# test_strip_v0_1_r1_1.net
KiCad netlist of a schematic drawn in EAGLE
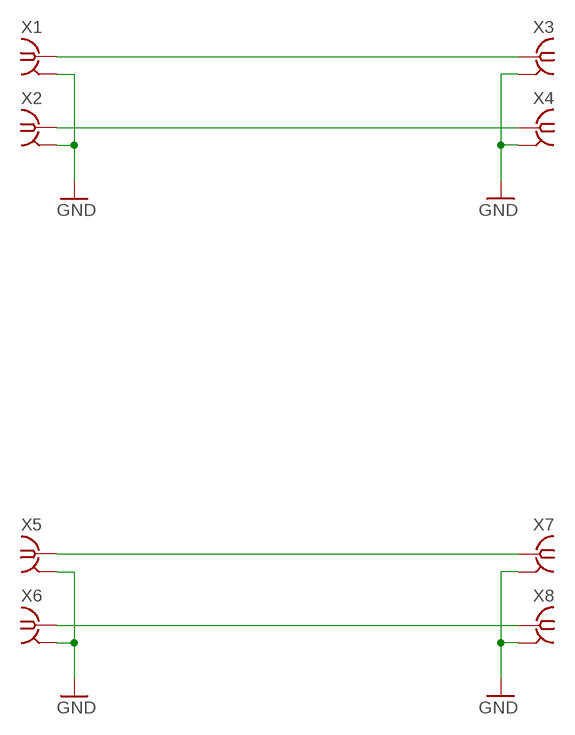
[diagram p0: schematic, sheet 1]

(export (version "E")
  (design (tool "Eeschema 10.0.6"))
  (components
    (comp (ref "X1")
      (value "BU-SMA-E-ND")
      (footprint "eagle-import:SMA-EDGE_ND")
      (libsource (lib "eagle-import") (part "BU-SMA-E-ND"))
    )
    (comp (ref "X2")
      (value "BU-SMA-E-ND")
      (footprint "eagle-import:SMA-EDGE_ND")
      (libsource (lib "eagle-import") (part "BU-SMA-E-ND"))
    )
    (comp (ref "X3")
      (value "BU-SMA-E-ND")
      (footprint "eagle-import:SMA-EDGE_ND")
      (libsource (lib "eagle-import") (part "BU-SMA-E-ND"))
    )
    (comp (ref "X4")
      (value "BU-SMA-E-ND")
      (footprint "eagle-import:SMA-EDGE_ND")
      (libsource (lib "eagle-import") (part "BU-SMA-E-ND"))
    )
    (comp (ref "X5")
      (value "BU-SMA-E-ND")
      (footprint "eagle-import:SMA-EDGE_ND")
      (libsource (lib "eagle-import") (part "BU-SMA-E-ND"))
    )
    (comp (ref "X6")
      (value "BU-SMA-E-ND")
      (footprint "eagle-import:SMA-EDGE_ND")
      (libsource (lib "eagle-import") (part "BU-SMA-E-ND"))
    )
    (comp (ref "X7")
      (value "BU-SMA-E-ND")
      (footprint "eagle-import:SMA-EDGE_ND")
      (libsource (lib "eagle-import") (part "BU-SMA-E-ND"))
    )
    (comp (ref "X8")
      (value "BU-SMA-E-ND")
      (footprint "eagle-import:SMA-EDGE_ND")
      (libsource (lib "eagle-import") (part "BU-SMA-E-ND"))
    )
  )
  (nets
    (net (code "1") (name "GND") (class "Default")
      (node (ref "X1") (pin "2@3") (pinfunction "2_2@3") (pintype "passive"))
      (node (ref "X1") (pin "2@4") (pinfunction "2_2@4") (pintype "passive"))
      (node (ref "X2") (pin "2@3") (pinfunction "2_2@3") (pintype "passive"))
      (node (ref "X2") (pin "2@4") (pinfunction "2_2@4") (pintype "passive"))
      (node (ref "X3") (pin "2@3") (pinfunction "2_2@3") (pintype "passive"))
      (node (ref "X3") (pin "2@4") (pinfunction "2_2@4") (pintype "passive"))
      (node (ref "X4") (pin "2@3") (pinfunction "2_2@3") (pintype "passive"))
      (node (ref "X4") (pin "2@4") (pinfunction "2_2@4") (pintype "passive"))
      (node (ref "X5") (pin "2@3") (pinfunction "2_2@3") (pintype "passive"))
      (node (ref "X5") (pin "2@4") (pinfunction "2_2@4") (pintype "passive"))
      (node (ref "X6") (pin "2@3") (pinfunction "2_2@3") (pintype "passive"))
      (node (ref "X6") (pin "2@4") (pinfunction "2_2@4") (pintype "passive"))
      (node (ref "X7") (pin "2@3") (pinfunction "2_2@3") (pintype "passive"))
      (node (ref "X7") (pin "2@4") (pinfunction "2_2@4") (pintype "passive"))
      (node (ref "X8") (pin "2@3") (pinfunction "2_2@3") (pintype "passive"))
      (node (ref "X8") (pin "2@4") (pinfunction "2_2@4") (pintype "passive"))
    )
    (net (code "2") (name "Net-(X1-Pad1)") (class "Default")
      (node (ref "X1") (pin "1") (pinfunction "1_1") (pintype "passive"))
      (node (ref "X3") (pin "1") (pinfunction "1_1") (pintype "passive"))
    )
    (net (code "3") (name "Net-(X2-Pad1)") (class "Default")
      (node (ref "X2") (pin "1") (pinfunction "1_1") (pintype "passive"))
      (node (ref "X4") (pin "1") (pinfunction "1_1") (pintype "passive"))
    )
    (net (code "4") (name "Net-(X5-Pad1)") (class "Default")
      (node (ref "X5") (pin "1") (pinfunction "1_1") (pintype "passive"))
      (node (ref "X7") (pin "1") (pinfunction "1_1") (pintype "passive"))
    )
    (net (code "5") (name "Net-(X6-Pad1)") (class "Default")
      (node (ref "X6") (pin "1") (pinfunction "1_1") (pintype "passive"))
      (node (ref "X8") (pin "1") (pinfunction "1_1") (pintype "passive"))
    )
  )
)
